# fpga_misc.net
KiCad netlist of a schematic drawn in Altium Designer
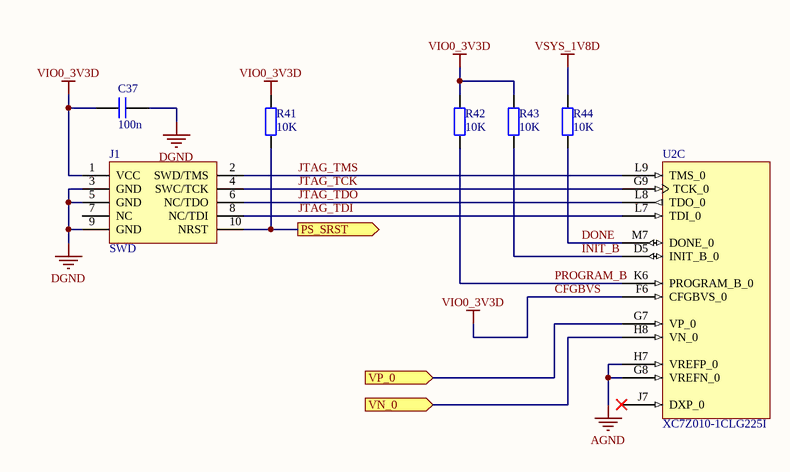
[diagram p0: fpga_misc.SchDoc]

(export (version "E")
  (design (tool "Eeschema 10.0.6"))
  (components
    (comp (ref "C37")
      (value "100n")
      (footprint "CAPC1005X06N")
      (description "Capacitor")
      (fields (field (name "Comment") "cap"))
      (libsource (lib "lib_passives") (part "cap"))
    )
    (comp (ref "J1")
      (value "SWD")
      (footprint "hdr_2x5_50mil")
      (description "SWD Header")
      (libsource (lib "lib_connectors") (part "hdr_swd"))
    )
    (comp (ref "R41")
      (value "10K")
      (footprint "RESC1005X04N")
      (description "Resistor")
      (fields (field (name "Comment") "res"))
      (libsource (lib "lib_passives") (part "res"))
    )
    (comp (ref "R42")
      (value "10K")
      (footprint "RESC1005X04N")
      (description "Resistor")
      (fields (field (name "Comment") "res"))
      (libsource (lib "lib_passives") (part "res"))
    )
    (comp (ref "R43")
      (value "10K")
      (footprint "RESC1005X04N")
      (description "Resistor")
      (fields (field (name "Comment") "res"))
      (libsource (lib "lib_passives") (part "res"))
    )
    (comp (ref "R44")
      (value "10K")
      (footprint "RESC1005X04N")
      (description "Resistor")
      (fields (field (name "Comment") "res"))
      (libsource (lib "lib_passives") (part "res"))
    )
    (comp (ref "U2")
      (value "XC7Z010-1CLG225I")
      (footprint "CLG225")
      (fields (field (name "GENERIC PART NUMBER") "XC7Z010"))
      (libsource (lib "Altium Content Vault") (part "XNLX-XC7Z010-CLG225"))
    )
  )
  (nets
    (net (code "1") (name "/DONE") (class "Default")
      (node (ref "R44") (pin "1") (pinfunction "1_1") (pintype "passive"))
      (node (ref "U2") (pin "M7") (pinfunction "DONE_0_M7") (pintype "bidirectional"))
    )
    (net (code "2") (name "/INIT_B") (class "Default")
      (node (ref "R43") (pin "1") (pinfunction "1_1") (pintype "passive"))
      (node (ref "U2") (pin "D5") (pinfunction "INIT_B_0_D5") (pintype "bidirectional"))
    )
    (net (code "3") (name "/JTAG_TCK") (class "Default")
      (node (ref "J1") (pin "4") (pinfunction "SWC/TCK_4") (pintype "passive"))
      (node (ref "U2") (pin "G9") (pinfunction "TCK_0_G9") (pintype "input"))
    )
    (net (code "4") (name "/JTAG_TDI") (class "Default")
      (node (ref "J1") (pin "8") (pinfunction "NC/TDI_8") (pintype "passive"))
      (node (ref "U2") (pin "L7") (pinfunction "TDI_0_L7") (pintype "input"))
    )
    (net (code "5") (name "/JTAG_TDO") (class "Default")
      (node (ref "J1") (pin "6") (pinfunction "NC/TDO_6") (pintype "passive"))
      (node (ref "U2") (pin "L8") (pinfunction "TDO_0_L8") (pintype "output"))
    )
    (net (code "6") (name "/JTAG_TMS") (class "Default")
      (node (ref "J1") (pin "2") (pinfunction "SWD/TMS_2") (pintype "passive"))
      (node (ref "U2") (pin "L9") (pinfunction "TMS_0_L9") (pintype "input"))
    )
    (net (code "7") (name "/PROGRAM_B") (class "Default")
      (node (ref "R42") (pin "1") (pinfunction "1_1") (pintype "passive"))
      (node (ref "U2") (pin "K6") (pinfunction "PROGRAM_B_0_K6") (pintype "input"))
    )
    (net (code "8") (name "/PS_SRST") (class "Default")
      (node (ref "J1") (pin "10") (pinfunction "NRST_10") (pintype "passive"))
      (node (ref "R41") (pin "1") (pinfunction "1_1") (pintype "passive"))
    )
    (net (code "9") (name "/VN_0") (class "Default")
      (node (ref "U2") (pin "H8") (pinfunction "VN_0_H8") (pintype "input"))
    )
    (net (code "10") (name "/VP_0") (class "Default")
      (node (ref "U2") (pin "G7") (pinfunction "VP_0_G7") (pintype "input"))
    )
    (net (code "11") (name "AGND") (class "Default")
      (node (ref "U2") (pin "G8") (pinfunction "VREFN_0_G8") (pintype "input"))
      (node (ref "U2") (pin "H7") (pinfunction "VREFP_0_H7") (pintype "input"))
    )
    (net (code "12") (name "DGND") (class "Default")
      (node (ref "C37") (pin "2") (pinfunction "2_2") (pintype "passive"))
      (node (ref "J1") (pin "3") (pinfunction "GND_3") (pintype "passive"))
      (node (ref "J1") (pin "5") (pinfunction "GND_5") (pintype "passive"))
      (node (ref "J1") (pin "9") (pinfunction "GND_9") (pintype "passive"))
    )
    (net (code "13") (name "VIO0_3V3D") (class "Default")
      (node (ref "C37") (pin "1") (pinfunction "1_1") (pintype "passive"))
      (node (ref "J1") (pin "1") (pinfunction "VCC_1") (pintype "passive"))
      (node (ref "R41") (pin "2") (pinfunction "2_2") (pintype "passive"))
      (node (ref "R42") (pin "2") (pinfunction "2_2") (pintype "passive"))
      (node (ref "R43") (pin "2") (pinfunction "2_2") (pintype "passive"))
      (node (ref "U2") (pin "F6") (pinfunction "CFGBVS_0_F6") (pintype "input"))
    )
    (net (code "14") (name "VSYS_1V8D") (class "Default")
      (node (ref "R44") (pin "2") (pinfunction "2_2") (pintype "passive"))
    )
    (net (code "15") (name "unconnected-(J1-NC-Pad7)") (class "Default")
      (node (ref "J1") (pin "7") (pinfunction "NC_7") (pintype "passive"))
    )
    (net (code "16") (name "unconnected-(U2C-DXP_0-PadJ7)") (class "Default")
      (node (ref "U2") (pin "J7") (pinfunction "DXP_0_J7") (pintype "input+no_connect"))
    )
  )
)
